# wd-g0906wy.net
KiCad netlist of a schematic drawn in EAGLE
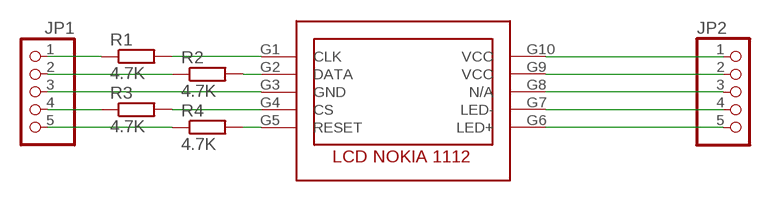
[diagram p0: schematic, sheet 1]

(export (version "E")
  (design (tool "Eeschema 10.0.6"))
  (components
    (comp (ref "HG1")
      (value "WD-G0906WY")
      (footprint "eagle-import:WD-G0906WY")
      (libsource (lib "eagle-import") (part "WD-G0906WY"))
    )
    (comp (ref "JP1")
      (value "PINHD-1X5")
      (footprint "eagle-import:1X05")
      (libsource (lib "eagle-import") (part "PINHD-1X5"))
    )
    (comp (ref "JP2")
      (value "PINHD-1X5")
      (footprint "eagle-import:1X05")
      (libsource (lib "eagle-import") (part "PINHD-1X5"))
    )
    (comp (ref "R1")
      (value "4.7K")
      (footprint "eagle-import:R1206")
      (libsource (lib "eagle-import") (part "R-EU_R1206"))
    )
    (comp (ref "R2")
      (value "4.7K")
      (footprint "eagle-import:R1206")
      (libsource (lib "eagle-import") (part "R-EU_R1206"))
    )
    (comp (ref "R3")
      (value "4.7K")
      (footprint "eagle-import:R1206")
      (libsource (lib "eagle-import") (part "R-EU_R1206"))
    )
    (comp (ref "R4")
      (value "4.7K")
      (footprint "eagle-import:R1206")
      (libsource (lib "eagle-import") (part "R-EU_R1206"))
    )
  )
  (nets
    (net (code "1") (name "Net-(HG1-CLK)") (class "Default")
      (node (ref "HG1") (pin "G1") (pinfunction "CLK_G1") (pintype "bidirectional"))
      (node (ref "R1") (pin "2") (pinfunction "2_2") (pintype "passive"))
    )
    (net (code "2") (name "Net-(HG1-CS)") (class "Default")
      (node (ref "HG1") (pin "G4") (pinfunction "CS_G4") (pintype "bidirectional"))
      (node (ref "R3") (pin "2") (pinfunction "2_2") (pintype "passive"))
    )
    (net (code "3") (name "Net-(HG1-DATA)") (class "Default")
      (node (ref "HG1") (pin "G2") (pinfunction "DATA_G2") (pintype "bidirectional"))
      (node (ref "R2") (pin "2") (pinfunction "2_2") (pintype "passive"))
    )
    (net (code "4") (name "Net-(HG1-GND)") (class "Default")
      (node (ref "HG1") (pin "G3") (pinfunction "GND_G3") (pintype "bidirectional"))
      (node (ref "JP1") (pin "3") (pinfunction "3_3") (pintype "passive"))
    )
    (net (code "5") (name "Net-(HG1-LED+)") (class "Default")
      (node (ref "HG1") (pin "G6") (pinfunction "LED+_G6") (pintype "bidirectional"))
      (node (ref "JP2") (pin "5") (pinfunction "5_5") (pintype "passive"))
    )
    (net (code "6") (name "Net-(HG1-LED-)") (class "Default")
      (node (ref "HG1") (pin "G7") (pinfunction "LED-_G7") (pintype "bidirectional"))
      (node (ref "JP2") (pin "4") (pinfunction "4_4") (pintype "passive"))
    )
    (net (code "7") (name "Net-(HG1-N{slash}A)") (class "Default")
      (node (ref "HG1") (pin "G8") (pinfunction "N/A_G8") (pintype "bidirectional"))
      (node (ref "JP2") (pin "3") (pinfunction "3_3") (pintype "passive"))
    )
    (net (code "8") (name "Net-(HG1-RESET)") (class "Default")
      (node (ref "HG1") (pin "G5") (pinfunction "RESET_G5") (pintype "bidirectional"))
      (node (ref "R4") (pin "2") (pinfunction "2_2") (pintype "passive"))
    )
    (net (code "9") (name "Net-(HG1-VCC-PadG9)") (class "Default")
      (node (ref "HG1") (pin "G9") (pinfunction "VCC_G9") (pintype "bidirectional"))
      (node (ref "JP2") (pin "2") (pinfunction "2_2") (pintype "passive"))
    )
    (net (code "10") (name "Net-(HG1-VCC-PadG10)") (class "Default")
      (node (ref "HG1") (pin "G10") (pinfunction "VCC_G10") (pintype "bidirectional"))
      (node (ref "JP2") (pin "1") (pinfunction "1_1") (pintype "passive"))
    )
    (net (code "11") (name "Net-(JP1-Pad1)") (class "Default")
      (node (ref "JP1") (pin "1") (pinfunction "1_1") (pintype "passive"))
      (node (ref "R1") (pin "1") (pinfunction "1_1") (pintype "passive"))
    )
    (net (code "12") (name "Net-(JP1-Pad2)") (class "Default")
      (node (ref "JP1") (pin "2") (pinfunction "2_2") (pintype "passive"))
      (node (ref "R2") (pin "1") (pinfunction "1_1") (pintype "passive"))
    )
    (net (code "13") (name "Net-(JP1-Pad4)") (class "Default")
      (node (ref "JP1") (pin "4") (pinfunction "4_4") (pintype "passive"))
      (node (ref "R3") (pin "1") (pinfunction "1_1") (pintype "passive"))
    )
    (net (code "14") (name "Net-(JP1-Pad5)") (class "Default")
      (node (ref "JP1") (pin "5") (pinfunction "5_5") (pintype "passive"))
      (node (ref "R4") (pin "1") (pinfunction "1_1") (pintype "passive"))
    )
  )
)
